# conn_board_adc.net
KiCad netlist of a schematic drawn in Altium Designer
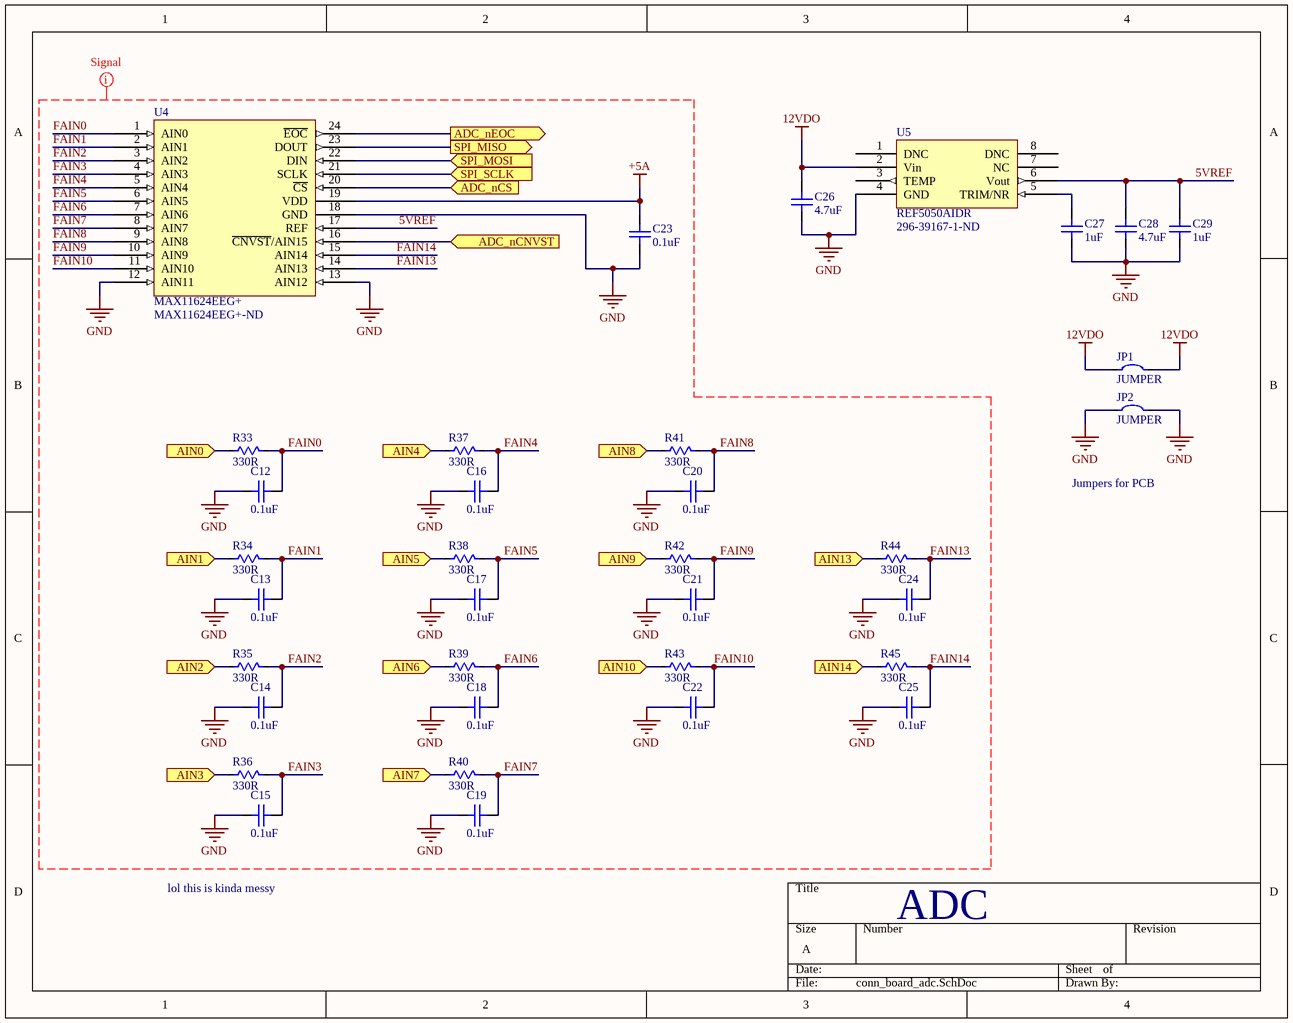
[diagram p0: conn_board_adc.SchDoc]

(export (version "E")
  (design (tool "Eeschema 10.0.6"))
  (components
    (comp (ref "C12")
      (value "0.1uF")
      (footprint "CAP_0805")
      (description "CAP CER 0.1UF 25V X7R 0805")
      (fields
        (field (name "MANUFACTURER") "KEMET")
        (field (name "MANUFACTURER PART NUMBER") "C0805C104M3RACTU")
      )
      (libsource (lib "Schlib1") (part "C0805C104M3RACTU"))
    )
    (comp (ref "C13")
      (value "0.1uF")
      (footprint "CAP_0805")
      (description "CAP CER 0.1UF 25V X7R 0805")
      (fields
        (field (name "MANUFACTURER") "KEMET")
        (field (name "MANUFACTURER PART NUMBER") "C0805C104M3RACTU")
      )
      (libsource (lib "Schlib1") (part "C0805C104M3RACTU"))
    )
    (comp (ref "C14")
      (value "0.1uF")
      (footprint "CAP_0805")
      (description "CAP CER 0.1UF 25V X7R 0805")
      (fields
        (field (name "MANUFACTURER") "KEMET")
        (field (name "MANUFACTURER PART NUMBER") "C0805C104M3RACTU")
      )
      (libsource (lib "Schlib1") (part "C0805C104M3RACTU"))
    )
    (comp (ref "C15")
      (value "0.1uF")
      (footprint "CAP_0805")
      (description "CAP CER 0.1UF 25V X7R 0805")
      (fields
        (field (name "MANUFACTURER") "KEMET")
        (field (name "MANUFACTURER PART NUMBER") "C0805C104M3RACTU")
      )
      (libsource (lib "Schlib1") (part "C0805C104M3RACTU"))
    )
    (comp (ref "C16")
      (value "0.1uF")
      (footprint "CAP_0805")
      (description "CAP CER 0.1UF 25V X7R 0805")
      (fields
        (field (name "MANUFACTURER") "KEMET")
        (field (name "MANUFACTURER PART NUMBER") "C0805C104M3RACTU")
      )
      (libsource (lib "Schlib1") (part "C0805C104M3RACTU"))
    )
    (comp (ref "C17")
      (value "0.1uF")
      (footprint "CAP_0805")
      (description "CAP CER 0.1UF 25V X7R 0805")
      (fields
        (field (name "MANUFACTURER") "KEMET")
        (field (name "MANUFACTURER PART NUMBER") "C0805C104M3RACTU")
      )
      (libsource (lib "Schlib1") (part "C0805C104M3RACTU"))
    )
    (comp (ref "C18")
      (value "0.1uF")
      (footprint "CAP_0805")
      (description "CAP CER 0.1UF 25V X7R 0805")
      (fields
        (field (name "MANUFACTURER") "KEMET")
        (field (name "MANUFACTURER PART NUMBER") "C0805C104M3RACTU")
      )
      (libsource (lib "Schlib1") (part "C0805C104M3RACTU"))
    )
    (comp (ref "C19")
      (value "0.1uF")
      (footprint "CAP_0805")
      (description "CAP CER 0.1UF 25V X7R 0805")
      (fields
        (field (name "MANUFACTURER") "KEMET")
        (field (name "MANUFACTURER PART NUMBER") "C0805C104M3RACTU")
      )
      (libsource (lib "Schlib1") (part "C0805C104M3RACTU"))
    )
    (comp (ref "C20")
      (value "0.1uF")
      (footprint "CAP_0805")
      (description "CAP CER 0.1UF 25V X7R 0805")
      (fields
        (field (name "MANUFACTURER") "KEMET")
        (field (name "MANUFACTURER PART NUMBER") "C0805C104M3RACTU")
      )
      (libsource (lib "Schlib1") (part "C0805C104M3RACTU"))
    )
    (comp (ref "C21")
      (value "0.1uF")
      (footprint "CAP_0805")
      (description "CAP CER 0.1UF 25V X7R 0805")
      (fields
        (field (name "MANUFACTURER") "KEMET")
        (field (name "MANUFACTURER PART NUMBER") "C0805C104M3RACTU")
      )
      (libsource (lib "Schlib1") (part "C0805C104M3RACTU"))
    )
    (comp (ref "C22")
      (value "0.1uF")
      (footprint "CAP_0805")
      (description "CAP CER 0.1UF 25V X7R 0805")
      (fields
        (field (name "MANUFACTURER") "KEMET")
        (field (name "MANUFACTURER PART NUMBER") "C0805C104M3RACTU")
      )
      (libsource (lib "Schlib1") (part "C0805C104M3RACTU"))
    )
    (comp (ref "C23")
      (value "0.1uF")
      (footprint "CAP_0805")
      (description "CAP CER 0.1UF 25V X7R 0805")
      (fields
        (field (name "MANUFACTURER") "KEMET")
        (field (name "MANUFACTURER PART NUMBER") "C0805C104M3RACTU")
      )
      (libsource (lib "Schlib1") (part "C0805C104M3RACTU"))
    )
    (comp (ref "C24")
      (value "0.1uF")
      (footprint "CAP_0805")
      (description "CAP CER 0.1UF 25V X7R 0805")
      (fields
        (field (name "MANUFACTURER") "KEMET")
        (field (name "MANUFACTURER PART NUMBER") "C0805C104M3RACTU")
      )
      (libsource (lib "Schlib1") (part "C0805C104M3RACTU"))
    )
    (comp (ref "C25")
      (value "0.1uF")
      (footprint "CAP_0805")
      (description "CAP CER 0.1UF 25V X7R 0805")
      (fields
        (field (name "MANUFACTURER") "KEMET")
        (field (name "MANUFACTURER PART NUMBER") "C0805C104M3RACTU")
      )
      (libsource (lib "Schlib1") (part "C0805C104M3RACTU"))
    )
    (comp (ref "C26")
      (value "4.7uF")
      (footprint "CAP_0805")
      (fields
        (field (name "MANUFACTURER") "Samsung")
        (field (name "MANUFACTURER PART NUMBER") "CL21A475KAQNNNE")
        (field (name "TOLERANCE") "10%")
      )
      (libsource (lib "Schlib1") (part "CL21A475KAQNNNE"))
    )
    (comp (ref "C27")
      (value "1uF")
      (footprint "CAP_0805")
      (description "Cap Ceramic 1uF 16V Y5V -20% to 80% Pad SMD 0805 85C T/R")
      (fields
        (field (name "MANUFACTURER") "KEMET")
        (field (name "MANUFACTURER PART NUMBER") "C0805C105Z4VACTU")
      )
      (libsource (lib "Schlib1") (part "C0805C105Z4VACTU"))
    )
    (comp (ref "C28")
      (value "4.7uF")
      (footprint "CAP_0805")
      (fields
        (field (name "MANUFACTURER") "Samsung")
        (field (name "MANUFACTURER PART NUMBER") "CL21A475KAQNNNE")
        (field (name "TOLERANCE") "10%")
      )
      (libsource (lib "Schlib1") (part "CL21A475KAQNNNE"))
    )
    (comp (ref "C29")
      (value "1uF")
      (footprint "CAP_0805")
      (description "Cap Ceramic 1uF 16V Y5V -20% to 80% Pad SMD 0805 85C T/R")
      (fields
        (field (name "MANUFACTURER") "KEMET")
        (field (name "MANUFACTURER PART NUMBER") "C0805C105Z4VACTU")
      )
      (libsource (lib "Schlib1") (part "C0805C105Z4VACTU"))
    )
    (comp (ref "JP1") (value "JUMPER") (footprint "JMP_20MM") (libsource (lib "Schlib1") (part "JUMPER")))
    (comp (ref "JP2") (value "JUMPER") (footprint "JMP_20MM") (libsource (lib "Schlib1") (part "JUMPER")))
    (comp (ref "R33")
      (value "330R")
      (footprint "RES_0805_PANASONIC")
      (description "Res Thin Film 0805 330 Ohm 0.5% 0.125W(1/8W) ±25ppm/C Molded SMD Automotive Punched T/R")
      (fields
        (field (name "MANUFACTURER") "Panasonic")
        (field (name "MANUFACTURER PART NUMBER") "ERA-6AED331V")
      )
      (libsource (lib "Schlib1") (part "ERA-6AED331V"))
    )
    (comp (ref "R34")
      (value "330R")
      (footprint "RES_0805_PANASONIC")
      (description "Res Thin Film 0805 330 Ohm 0.5% 0.125W(1/8W) ±25ppm/C Molded SMD Automotive Punched T/R")
      (fields
        (field (name "MANUFACTURER") "Panasonic")
        (field (name "MANUFACTURER PART NUMBER") "ERA-6AED331V")
      )
      (libsource (lib "Schlib1") (part "ERA-6AED331V"))
    )
    (comp (ref "R35")
      (value "330R")
      (footprint "RES_0805_PANASONIC")
      (description "Res Thin Film 0805 330 Ohm 0.5% 0.125W(1/8W) ±25ppm/C Molded SMD Automotive Punched T/R")
      (fields
        (field (name "MANUFACTURER") "Panasonic")
        (field (name "MANUFACTURER PART NUMBER") "ERA-6AED331V")
      )
      (libsource (lib "Schlib1") (part "ERA-6AED331V"))
    )
    (comp (ref "R36")
      (value "330R")
      (footprint "RES_0805_PANASONIC")
      (description "Res Thin Film 0805 330 Ohm 0.5% 0.125W(1/8W) ±25ppm/C Molded SMD Automotive Punched T/R")
      (fields
        (field (name "MANUFACTURER") "Panasonic")
        (field (name "MANUFACTURER PART NUMBER") "ERA-6AED331V")
      )
      (libsource (lib "Schlib1") (part "ERA-6AED331V"))
    )
    (comp (ref "R37")
      (value "330R")
      (footprint "RES_0805_PANASONIC")
      (description "Res Thin Film 0805 330 Ohm 0.5% 0.125W(1/8W) ±25ppm/C Molded SMD Automotive Punched T/R")
      (fields
        (field (name "MANUFACTURER") "Panasonic")
        (field (name "MANUFACTURER PART NUMBER") "ERA-6AED331V")
      )
      (libsource (lib "Schlib1") (part "ERA-6AED331V"))
    )
    (comp (ref "R38")
      (value "330R")
      (footprint "RES_0805_PANASONIC")
      (description "Res Thin Film 0805 330 Ohm 0.5% 0.125W(1/8W) ±25ppm/C Molded SMD Automotive Punched T/R")
      (fields
        (field (name "MANUFACTURER") "Panasonic")
        (field (name "MANUFACTURER PART NUMBER") "ERA-6AED331V")
      )
      (libsource (lib "Schlib1") (part "ERA-6AED331V"))
    )
    (comp (ref "R39")
      (value "330R")
      (footprint "RES_0805_PANASONIC")
      (description "Res Thin Film 0805 330 Ohm 0.5% 0.125W(1/8W) ±25ppm/C Molded SMD Automotive Punched T/R")
      (fields
        (field (name "MANUFACTURER") "Panasonic")
        (field (name "MANUFACTURER PART NUMBER") "ERA-6AED331V")
      )
      (libsource (lib "Schlib1") (part "ERA-6AED331V"))
    )
    (comp (ref "R40")
      (value "330R")
      (footprint "RES_0805_PANASONIC")
      (description "Res Thin Film 0805 330 Ohm 0.5% 0.125W(1/8W) ±25ppm/C Molded SMD Automotive Punched T/R")
      (fields
        (field (name "MANUFACTURER") "Panasonic")
        (field (name "MANUFACTURER PART NUMBER") "ERA-6AED331V")
      )
      (libsource (lib "Schlib1") (part "ERA-6AED331V"))
    )
    (comp (ref "R41")
      (value "330R")
      (footprint "RES_0805_PANASONIC")
      (description "Res Thin Film 0805 330 Ohm 0.5% 0.125W(1/8W) ±25ppm/C Molded SMD Automotive Punched T/R")
      (fields
        (field (name "MANUFACTURER") "Panasonic")
        (field (name "MANUFACTURER PART NUMBER") "ERA-6AED331V")
      )
      (libsource (lib "Schlib1") (part "ERA-6AED331V"))
    )
    (comp (ref "R42")
      (value "330R")
      (footprint "RES_0805_PANASONIC")
      (description "Res Thin Film 0805 330 Ohm 0.5% 0.125W(1/8W) ±25ppm/C Molded SMD Automotive Punched T/R")
      (fields
        (field (name "MANUFACTURER") "Panasonic")
        (field (name "MANUFACTURER PART NUMBER") "ERA-6AED331V")
      )
      (libsource (lib "Schlib1") (part "ERA-6AED331V"))
    )
    (comp (ref "R43")
      (value "330R")
      (footprint "RES_0805_PANASONIC")
      (description "Res Thin Film 0805 330 Ohm 0.5% 0.125W(1/8W) ±25ppm/C Molded SMD Automotive Punched T/R")
      (fields
        (field (name "MANUFACTURER") "Panasonic")
        (field (name "MANUFACTURER PART NUMBER") "ERA-6AED331V")
      )
      (libsource (lib "Schlib1") (part "ERA-6AED331V"))
    )
    (comp (ref "R44")
      (value "330R")
      (footprint "RES_0805_PANASONIC")
      (description "Res Thin Film 0805 330 Ohm 0.5% 0.125W(1/8W) ±25ppm/C Molded SMD Automotive Punched T/R")
      (fields
        (field (name "MANUFACTURER") "Panasonic")
        (field (name "MANUFACTURER PART NUMBER") "ERA-6AED331V")
      )
      (libsource (lib "Schlib1") (part "ERA-6AED331V"))
    )
    (comp (ref "R45")
      (value "330R")
      (footprint "RES_0805_PANASONIC")
      (description "Res Thin Film 0805 330 Ohm 0.5% 0.125W(1/8W) ±25ppm/C Molded SMD Automotive Punched T/R")
      (fields
        (field (name "MANUFACTURER") "Panasonic")
        (field (name "MANUFACTURER PART NUMBER") "ERA-6AED331V")
      )
      (libsource (lib "Schlib1") (part "ERA-6AED331V"))
    )
    (comp (ref "U4")
      (value "MAX11624EEG+")
      (footprint "QSOP24")
      (description "GLOVE, POLYAMIDE, L/FREE, PU, SIZE 6 - More Details")
      (fields (field (name "MANUFACTURER") "Maxim") (field (name "SUPPLIER PART NUMBER 1") "MAX11624EEG+-ND"))
      (libsource (lib "Schlib1") (part "MAX11624EEG+"))
    )
    (comp (ref "U5")
      (value "REF5050AIDR")
      (footprint "SOIC_8")
      (description "TEXAS INSTRUMENTS - REF5050AIDR - VOLTAGE REF, SERIES, 5V, SOIC-8")
      (fields
        (field (name "MANUFACTURER") "Texas Instruments")
        (field (name "TOLERANCE") "0.1%")
        (field (name "SUPPLIER PART NUMBER 1") "296-39167-1-ND")
      )
      (libsource (lib "Schlib1") (part "REF5050AIDR"))
    )
  )
  (nets
    (net (code "1") (name "+5A") (class "Default")
      (node (ref "C23") (pin "1") (pinfunction "1_1") (pintype "passive"))
      (node (ref "U4") (pin "19") (pinfunction "VDD_19") (pintype "power_in"))
    )
    (net (code "2") (name "/5VREF") (class "Default")
      (node (ref "C28") (pin "2") (pinfunction "2_2") (pintype "passive"))
      (node (ref "C29") (pin "2") (pinfunction "2_2") (pintype "passive"))
      (node (ref "U4") (pin "17") (pinfunction "REF_17") (pintype "input"))
      (node (ref "U5") (pin "6") (pinfunction "Vout_6") (pintype "output"))
    )
    (net (code "3") (name "/ADC_nCNVST") (class "Default")
      (node (ref "U4") (pin "16") (pinfunction "~{CNVST}/AIN15_16") (pintype "input"))
    )
    (net (code "4") (name "/ADC_nCS") (class "Default")
      (node (ref "U4") (pin "20") (pinfunction "~{CS}_20") (pintype "input"))
    )
    (net (code "5") (name "/ADC_nEOC") (class "Default")
      (node (ref "U4") (pin "24") (pinfunction "~{EOC}_24") (pintype "output"))
    )
    (net (code "6") (name "/AIN0") (class "Default")
      (node (ref "R33") (pin "1") (pinfunction "1_1") (pintype "passive"))
    )
    (net (code "7") (name "/AIN1") (class "Default")
      (node (ref "R34") (pin "1") (pinfunction "1_1") (pintype "passive"))
    )
    (net (code "8") (name "/AIN2") (class "Default")
      (node (ref "R35") (pin "1") (pinfunction "1_1") (pintype "passive"))
    )
    (net (code "9") (name "/AIN3") (class "Default")
      (node (ref "R36") (pin "1") (pinfunction "1_1") (pintype "passive"))
    )
    (net (code "10") (name "/AIN4") (class "Default")
      (node (ref "R37") (pin "1") (pinfunction "1_1") (pintype "passive"))
    )
    (net (code "11") (name "/AIN5") (class "Default")
      (node (ref "R38") (pin "1") (pinfunction "1_1") (pintype "passive"))
    )
    (net (code "12") (name "/AIN6") (class "Default")
      (node (ref "R39") (pin "1") (pinfunction "1_1") (pintype "passive"))
    )
    (net (code "13") (name "/AIN7") (class "Default")
      (node (ref "R40") (pin "1") (pinfunction "1_1") (pintype "passive"))
    )
    (net (code "14") (name "/AIN8") (class "Default")
      (node (ref "R41") (pin "1") (pinfunction "1_1") (pintype "passive"))
    )
    (net (code "15") (name "/AIN9") (class "Default")
      (node (ref "R42") (pin "1") (pinfunction "1_1") (pintype "passive"))
    )
    (net (code "16") (name "/AIN10") (class "Default")
      (node (ref "R43") (pin "1") (pinfunction "1_1") (pintype "passive"))
    )
    (net (code "17") (name "/AIN13") (class "Default")
      (node (ref "R44") (pin "1") (pinfunction "1_1") (pintype "passive"))
    )
    (net (code "18") (name "/AIN14") (class "Default")
      (node (ref "R45") (pin "1") (pinfunction "1_1") (pintype "passive"))
    )
    (net (code "19") (name "/FAIN0") (class "Default")
      (node (ref "C12") (pin "2") (pinfunction "2_2") (pintype "passive"))
      (node (ref "R33") (pin "2") (pinfunction "2_2") (pintype "passive"))
      (node (ref "U4") (pin "1") (pinfunction "AIN0_1") (pintype "input"))
    )
    (net (code "20") (name "/FAIN1") (class "Default")
      (node (ref "C13") (pin "2") (pinfunction "2_2") (pintype "passive"))
      (node (ref "R34") (pin "2") (pinfunction "2_2") (pintype "passive"))
      (node (ref "U4") (pin "2") (pinfunction "AIN1_2") (pintype "input"))
    )
    (net (code "21") (name "/FAIN2") (class "Default")
      (node (ref "C14") (pin "2") (pinfunction "2_2") (pintype "passive"))
      (node (ref "R35") (pin "2") (pinfunction "2_2") (pintype "passive"))
      (node (ref "U4") (pin "3") (pinfunction "AIN2_3") (pintype "input"))
    )
    (net (code "22") (name "/FAIN3") (class "Default")
      (node (ref "C15") (pin "2") (pinfunction "2_2") (pintype "passive"))
      (node (ref "R36") (pin "2") (pinfunction "2_2") (pintype "passive"))
      (node (ref "U4") (pin "4") (pinfunction "AIN3_4") (pintype "input"))
    )
    (net (code "23") (name "/FAIN4") (class "Default")
      (node (ref "C16") (pin "2") (pinfunction "2_2") (pintype "passive"))
      (node (ref "R37") (pin "2") (pinfunction "2_2") (pintype "passive"))
      (node (ref "U4") (pin "5") (pinfunction "AIN4_5") (pintype "input"))
    )
    (net (code "24") (name "/FAIN5") (class "Default")
      (node (ref "C17") (pin "2") (pinfunction "2_2") (pintype "passive"))
      (node (ref "R38") (pin "2") (pinfunction "2_2") (pintype "passive"))
      (node (ref "U4") (pin "6") (pinfunction "AIN5_6") (pintype "input"))
    )
    (net (code "25") (name "/FAIN6") (class "Default")
      (node (ref "C18") (pin "2") (pinfunction "2_2") (pintype "passive"))
      (node (ref "R39") (pin "2") (pinfunction "2_2") (pintype "passive"))
      (node (ref "U4") (pin "7") (pinfunction "AIN6_7") (pintype "input"))
    )
    (net (code "26") (name "/FAIN7") (class "Default")
      (node (ref "C19") (pin "2") (pinfunction "2_2") (pintype "passive"))
      (node (ref "R40") (pin "2") (pinfunction "2_2") (pintype "passive"))
      (node (ref "U4") (pin "8") (pinfunction "AIN7_8") (pintype "input"))
    )
    (net (code "27") (name "/FAIN8") (class "Default")
      (node (ref "C20") (pin "2") (pinfunction "2_2") (pintype "passive"))
      (node (ref "R41") (pin "2") (pinfunction "2_2") (pintype "passive"))
      (node (ref "U4") (pin "9") (pinfunction "AIN8_9") (pintype "input"))
    )
    (net (code "28") (name "/FAIN9") (class "Default")
      (node (ref "C21") (pin "2") (pinfunction "2_2") (pintype "passive"))
      (node (ref "R42") (pin "2") (pinfunction "2_2") (pintype "passive"))
      (node (ref "U4") (pin "10") (pinfunction "AIN9_10") (pintype "input"))
    )
    (net (code "29") (name "/FAIN10") (class "Default")
      (node (ref "C22") (pin "2") (pinfunction "2_2") (pintype "passive"))
      (node (ref "R43") (pin "2") (pinfunction "2_2") (pintype "passive"))
      (node (ref "U4") (pin "11") (pinfunction "AIN10_11") (pintype "input"))
    )
    (net (code "30") (name "/FAIN13") (class "Default")
      (node (ref "C24") (pin "2") (pinfunction "2_2") (pintype "passive"))
      (node (ref "R44") (pin "2") (pinfunction "2_2") (pintype "passive"))
      (node (ref "U4") (pin "14") (pinfunction "AIN13_14") (pintype "input"))
    )
    (net (code "31") (name "/FAIN14") (class "Default")
      (node (ref "C25") (pin "2") (pinfunction "2_2") (pintype "passive"))
      (node (ref "R45") (pin "2") (pinfunction "2_2") (pintype "passive"))
      (node (ref "U4") (pin "15") (pinfunction "AIN14_15") (pintype "input"))
    )
    (net (code "32") (name "/SPI_MISO") (class "Default")
      (node (ref "U4") (pin "23") (pinfunction "DOUT_23") (pintype "output"))
    )
    (net (code "33") (name "/SPI_MOSI") (class "Default")
      (node (ref "U4") (pin "22") (pinfunction "DIN_22") (pintype "input"))
    )
    (net (code "34") (name "/SPI_SCLK") (class "Default")
      (node (ref "U4") (pin "21") (pinfunction "SCLK_21") (pintype "input"))
    )
    (net (code "35") (name "12VDO") (class "Default")
      (node (ref "C26") (pin "2") (pinfunction "2_2") (pintype "passive"))
      (node (ref "JP1") (pin "1") (pinfunction "1_1") (pintype "passive"))
      (node (ref "JP1") (pin "2") (pinfunction "2_2") (pintype "passive"))
      (node (ref "U5") (pin "2") (pinfunction "Vin_2") (pintype "power_in"))
    )
    (net (code "36") (name "GND") (class "Default")
      (node (ref "C12") (pin "1") (pinfunction "1_1") (pintype "passive"))
      (node (ref "C13") (pin "1") (pinfunction "1_1") (pintype "passive"))
      (node (ref "C14") (pin "1") (pinfunction "1_1") (pintype "passive"))
      (node (ref "C15") (pin "1") (pinfunction "1_1") (pintype "passive"))
      (node (ref "C16") (pin "1") (pinfunction "1_1") (pintype "passive"))
      (node (ref "C17") (pin "1") (pinfunction "1_1") (pintype "passive"))
      (node (ref "C18") (pin "1") (pinfunction "1_1") (pintype "passive"))
      (node (ref "C19") (pin "1") (pinfunction "1_1") (pintype "passive"))
      (node (ref "C20") (pin "1") (pinfunction "1_1") (pintype "passive"))
      (node (ref "C21") (pin "1") (pinfunction "1_1") (pintype "passive"))
      (node (ref "C22") (pin "1") (pinfunction "1_1") (pintype "passive"))
      (node (ref "C23") (pin "2") (pinfunction "2_2") (pintype "passive"))
      (node (ref "C24") (pin "1") (pinfunction "1_1") (pintype "passive"))
      (node (ref "C25") (pin "1") (pinfunction "1_1") (pintype "passive"))
      (node (ref "C26") (pin "1") (pinfunction "1_1") (pintype "passive"))
      (node (ref "C27") (pin "1") (pinfunction "1_1") (pintype "passive"))
      (node (ref "C28") (pin "1") (pinfunction "1_1") (pintype "passive"))
      (node (ref "C29") (pin "1") (pinfunction "1_1") (pintype "passive"))
      (node (ref "JP2") (pin "1") (pinfunction "1_1") (pintype "passive"))
      (node (ref "JP2") (pin "2") (pinfunction "2_2") (pintype "passive"))
      (node (ref "U4") (pin "12") (pinfunction "AIN11_12") (pintype "input"))
      (node (ref "U4") (pin "13") (pinfunction "AIN12_13") (pintype "input"))
      (node (ref "U4") (pin "18") (pinfunction "GND_18") (pintype "power_in"))
      (node (ref "U5") (pin "4") (pinfunction "GND_4") (pintype "power_in"))
    )
    (net (code "37") (name "Net-(U5-TRIM{slash}NR)") (class "Default")
      (node (ref "C27") (pin "2") (pinfunction "2_2") (pintype "passive"))
      (node (ref "U5") (pin "5") (pinfunction "TRIM/NR_5") (pintype "input"))
    )
    (net (code "38") (name "unconnected-(U5-DNC-Pad1)") (class "Default")
      (node (ref "U5") (pin "1") (pinfunction "DNC_1") (pintype "tri_state"))
    )
    (net (code "39") (name "unconnected-(U5-DNC-Pad8)") (class "Default")
      (node (ref "U5") (pin "8") (pinfunction "DNC_8") (pintype "tri_state"))
    )
    (net (code "40") (name "unconnected-(U5-NC-Pad7)") (class "Default")
      (node (ref "U5") (pin "7") (pinfunction "NC_7") (pintype "tri_state"))
    )
    (net (code "41") (name "unconnected-(U5-TEMP-Pad3)") (class "Default")
      (node (ref "U5") (pin "3") (pinfunction "TEMP_3") (pintype "output"))
    )
  )
)
